# reset.net
KiCad netlist of a schematic drawn in EAGLE
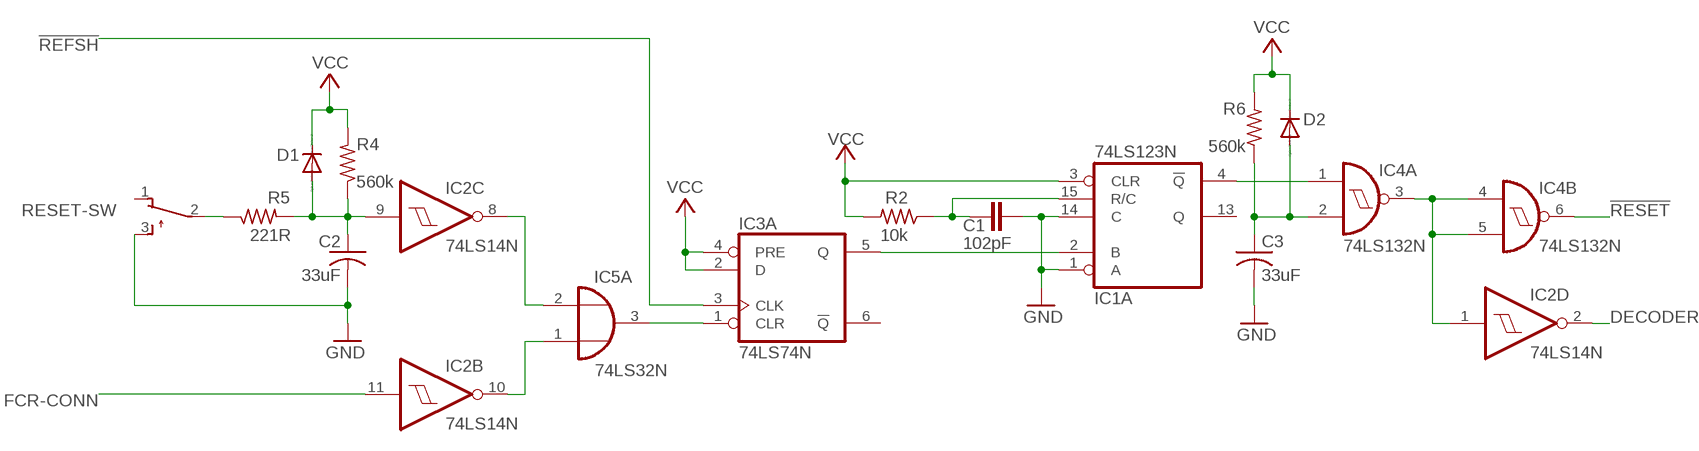
[diagram p0: schematic, sheet 1]

(export (version "E")
  (design (tool "Eeschema 10.0.6"))
  (components
    (comp (ref "C1")
      (value "102pF")
      (footprint "eagle-import:C025-030X050")
      (libsource (lib "eagle-import") (part "C-EU025-030X050"))
    )
    (comp (ref "C2")
      (value "33uF")
      (footprint "eagle-import:C025-030X050")
      (libsource (lib "eagle-import") (part "C-US025-030X050"))
    )
    (comp (ref "C3")
      (value "33uF")
      (footprint "eagle-import:C025-030X050")
      (libsource (lib "eagle-import") (part "C-US025-030X050"))
    )
    (comp (ref "D1")
      (value "1N4148DO35-10")
      (footprint "eagle-import:DO35-10")
      (libsource (lib "eagle-import") (part "1N4148DO35-10"))
    )
    (comp (ref "D2")
      (value "1N4148DO35-10")
      (footprint "eagle-import:DO35-10")
      (libsource (lib "eagle-import") (part "1N4148DO35-10"))
    )
    (comp (ref "IC1")
      (value "74LS123N")
      (footprint "eagle-import:DIL16")
      (libsource (lib "eagle-import") (part "74123NLS"))
    )
    (comp (ref "IC2")
      (value "74LS14N")
      (footprint "eagle-import:DIL14")
      (libsource (lib "eagle-import") (part "7414NLS"))
    )
    (comp (ref "IC3")
      (value "74LS74N")
      (footprint "eagle-import:DIL14")
      (libsource (lib "eagle-import") (part "7474NLS"))
    )
    (comp (ref "IC4")
      (value "74LS132N")
      (footprint "eagle-import:DIL14")
      (libsource (lib "eagle-import") (part "74132NLS"))
    )
    (comp (ref "IC5")
      (value "74LS32N")
      (footprint "eagle-import:DIL14")
      (libsource (lib "eagle-import") (part "7432NLS"))
    )
    (comp (ref "R2")
      (value "10k")
      (footprint "eagle-import:0204_7")
      (libsource (lib "eagle-import") (part "R-US_0204/7"))
    )
    (comp (ref "R4")
      (value "560k")
      (footprint "eagle-import:0204_7")
      (libsource (lib "eagle-import") (part "R-US_0204/7"))
    )
    (comp (ref "R5")
      (value "221R")
      (footprint "eagle-import:0204_7")
      (libsource (lib "eagle-import") (part "R-US_0204/7"))
    )
    (comp (ref "R6")
      (value "560k")
      (footprint "eagle-import:0204_7")
      (libsource (lib "eagle-import") (part "R-US_0204/7"))
    )
    (comp (ref "RESET-SW")
      (value "TL32PO")
      (footprint "eagle-import:TL3XPO")
      (libsource (lib "eagle-import") (part "TL32PO"))
    )
  )
  (nets
    (net (code "1") (name "/DECODER") (class "Default")
      (node (ref "IC2") (pin "2") (pinfunction "O_2") (pintype "output"))
    )
    (net (code "2") (name "/FCR-CONN") (class "Default")
      (node (ref "IC2") (pin "11") (pinfunction "I_11") (pintype "input"))
    )
    (net (code "3") (name "/~{REFSH}") (class "Default")
      (node (ref "IC3") (pin "3") (pinfunction "CLK_3") (pintype "input"))
    )
    (net (code "4") (name "/~{RESET}") (class "Default")
      (node (ref "IC4") (pin "6") (pinfunction "O_6") (pintype "output"))
    )
    (net (code "5") (name "GND") (class "Default")
      (node (ref "C1") (pin "1") (pinfunction "1_1") (pintype "passive"))
      (node (ref "C2") (pin "2") (pinfunction "2_2") (pintype "passive"))
      (node (ref "C3") (pin "2") (pinfunction "2_2") (pintype "passive"))
      (node (ref "IC1") (pin "1") (pinfunction "A_1") (pintype "input"))
      (node (ref "IC1") (pin "14") (pinfunction "C_14") (pintype "input"))
      (node (ref "RESET-SW") (pin "3") (pinfunction "S_3") (pintype "passive"))
    )
    (net (code "6") (name "Net-(IC1A-B)") (class "Default")
      (node (ref "IC1") (pin "2") (pinfunction "B_2") (pintype "input"))
      (node (ref "IC3") (pin "5") (pinfunction "Q_5") (pintype "output"))
    )
    (net (code "7") (name "Net-(IC1A-R{slash}C)") (class "Default")
      (node (ref "C1") (pin "2") (pinfunction "2_2") (pintype "passive"))
      (node (ref "IC1") (pin "15") (pinfunction "R/C_15") (pintype "input"))
      (node (ref "R2") (pin "1") (pinfunction "1_1") (pintype "passive"))
    )
    (net (code "8") (name "Net-(IC1A-~{Q})") (class "Default")
      (node (ref "IC1") (pin "4") (pinfunction "~{Q}_4") (pintype "output"))
      (node (ref "IC4") (pin "1") (pinfunction "I0_1") (pintype "input"))
    )
    (net (code "9") (name "Net-(IC2B-O)") (class "Default")
      (node (ref "IC2") (pin "10") (pinfunction "O_10") (pintype "output"))
      (node (ref "IC5") (pin "1") (pinfunction "I0_1") (pintype "input"))
    )
    (net (code "10") (name "Net-(IC2C-I)") (class "Default")
      (node (ref "C2") (pin "1") (pinfunction "1_1") (pintype "passive"))
      (node (ref "D1") (pin "A") (pinfunction "A_A") (pintype "passive"))
      (node (ref "IC2") (pin "9") (pinfunction "I_9") (pintype "input"))
      (node (ref "R4") (pin "1") (pinfunction "1_1") (pintype "passive"))
      (node (ref "R5") (pin "2") (pinfunction "2_2") (pintype "passive"))
    )
    (net (code "11") (name "Net-(IC2C-O)") (class "Default")
      (node (ref "IC2") (pin "8") (pinfunction "O_8") (pintype "output"))
      (node (ref "IC5") (pin "2") (pinfunction "I1_2") (pintype "input"))
    )
    (net (code "12") (name "Net-(IC2D-I)") (class "Default")
      (node (ref "IC2") (pin "1") (pinfunction "I_1") (pintype "input"))
      (node (ref "IC4") (pin "3") (pinfunction "O_3") (pintype "output"))
      (node (ref "IC4") (pin "4") (pinfunction "I0_4") (pintype "input"))
      (node (ref "IC4") (pin "5") (pinfunction "I1_5") (pintype "input"))
    )
    (net (code "13") (name "Net-(IC3A-CLR)") (class "Default")
      (node (ref "IC3") (pin "1") (pinfunction "CLR_1") (pintype "input"))
      (node (ref "IC5") (pin "3") (pinfunction "O_3") (pintype "output"))
    )
    (net (code "14") (name "Net-(IC4A-I1)") (class "Default")
      (node (ref "C3") (pin "1") (pinfunction "1_1") (pintype "passive"))
      (node (ref "D2") (pin "A") (pinfunction "A_A") (pintype "passive"))
      (node (ref "IC4") (pin "2") (pinfunction "I1_2") (pintype "input"))
      (node (ref "R6") (pin "1") (pinfunction "1_1") (pintype "passive"))
    )
    (net (code "15") (name "Net-(RESET-SW-P)") (class "Default")
      (node (ref "R5") (pin "1") (pinfunction "1_1") (pintype "passive"))
      (node (ref "RESET-SW") (pin "2") (pinfunction "P_2") (pintype "passive"))
    )
    (net (code "16") (name "VCC") (class "Default")
      (node (ref "D1") (pin "C") (pinfunction "C_C") (pintype "passive"))
      (node (ref "D2") (pin "C") (pinfunction "C_C") (pintype "passive"))
      (node (ref "IC1") (pin "3") (pinfunction "CLR_3") (pintype "input"))
      (node (ref "IC3") (pin "2") (pinfunction "D_2") (pintype "input"))
      (node (ref "IC3") (pin "4") (pinfunction "PRE_4") (pintype "input"))
      (node (ref "R2") (pin "2") (pinfunction "2_2") (pintype "passive"))
      (node (ref "R4") (pin "2") (pinfunction "2_2") (pintype "passive"))
      (node (ref "R6") (pin "2") (pinfunction "2_2") (pintype "passive"))
    )
    (net (code "17") (name "unconnected-(IC1A-Q-Pad13)") (class "Default")
      (node (ref "IC1") (pin "13") (pinfunction "Q_13") (pintype "output"))
    )
    (net (code "18") (name "unconnected-(IC3A-~{Q}-Pad6)") (class "Default")
      (node (ref "IC3") (pin "6") (pinfunction "~{Q}_6") (pintype "output"))
    )
    (net (code "19") (name "unconnected-(RESET-SW-O-Pad1)") (class "Default")
      (node (ref "RESET-SW") (pin "1") (pinfunction "O_1") (pintype "passive"))
    )
  )
)
